# introAu.net
KiCad netlist of a schematic drawn in EAGLE
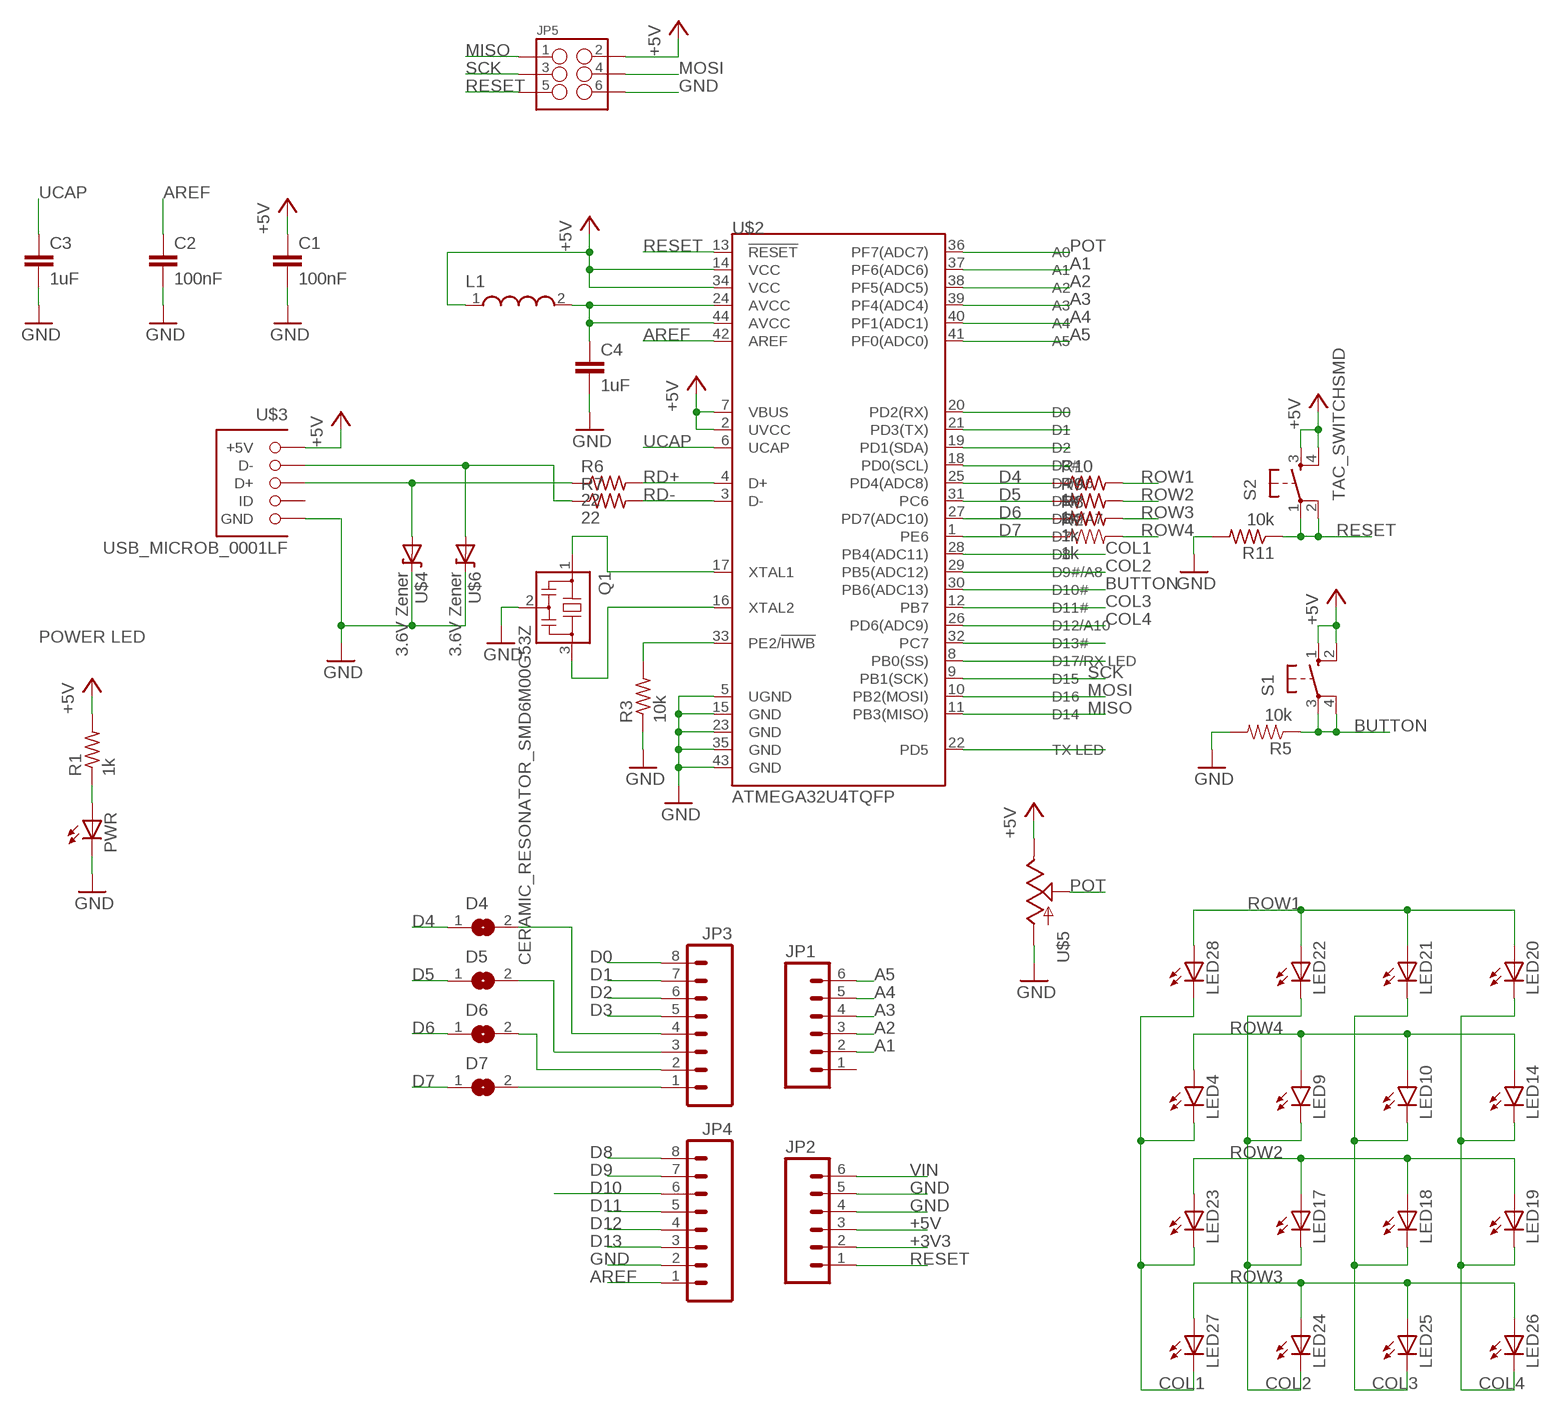
[diagram p0: schematic, sheet 1]

(export (version "E")
  (design (tool "Eeschema 10.0.6"))
  (components
    (comp (ref "C1")
      (value "100nF")
      (footprint "eagle-import:C0805")
      (libsource (lib "eagle-import") (part "C-EUC0805"))
    )
    (comp (ref "C2")
      (value "100nF")
      (footprint "eagle-import:C0805")
      (libsource (lib "eagle-import") (part "C-EUC0805"))
    )
    (comp (ref "C3")
      (value "1uF")
      (footprint "eagle-import:C0805")
      (libsource (lib "eagle-import") (part "C-EUC0805"))
    )
    (comp (ref "C4")
      (value "1uF")
      (footprint "eagle-import:C0805")
      (libsource (lib "eagle-import") (part "C-EUC0805"))
    )
    (comp (ref "D4") (value "SJ") (footprint "eagle-import:SJ") (libsource (lib "eagle-import") (part "SJ")))
    (comp (ref "D5") (value "SJ") (footprint "eagle-import:SJ") (libsource (lib "eagle-import") (part "SJ")))
    (comp (ref "D6") (value "SJ") (footprint "eagle-import:SJ") (libsource (lib "eagle-import") (part "SJ")))
    (comp (ref "D7") (value "SJ") (footprint "eagle-import:SJ") (libsource (lib "eagle-import") (part "SJ")))
    (comp (ref "JP1")
      (value "M06SMD-STRAIGHT-COMBO")
      (footprint "eagle-import:1X06_SMD_STRAIGHT_COMBO")
      (libsource (lib "eagle-import") (part "M06SMD-STRAIGHT-COMBO"))
    )
    (comp (ref "JP2")
      (value "M06SMD-STRAIGHT-COMBO")
      (footprint "eagle-import:1X06_SMD_STRAIGHT_COMBO")
      (libsource (lib "eagle-import") (part "M06SMD-STRAIGHT-COMBO"))
    )
    (comp (ref "JP3")
      (value "M08SMD-COMBO")
      (footprint "eagle-import:1X08_SMD_COMBINED")
      (libsource (lib "eagle-import") (part "M08SMD-COMBO"))
    )
    (comp (ref "JP4")
      (value "M08SMD-COMBO")
      (footprint "eagle-import:1X08_SMD_COMBINED")
      (libsource (lib "eagle-import") (part "M08SMD-COMBO"))
    )
    (comp (ref "JP5")
      (value "M03X22X3_SILK_SM")
      (footprint "eagle-import:2X3")
      (libsource (lib "eagle-import") (part "M03X22X3_SILK_SM"))
    )
    (comp (ref "L1")
      (value "WE-CBF_0805(WB/HS)")
      (footprint "eagle-import:WE-CBF_0805(W=3.0)")
      (libsource (lib "eagle-import") (part "WE-CBF_0805(WB/HS)"))
    )
    (comp (ref "LED4")
      (value "LED5MM")
      (footprint "eagle-import:LED5MM")
      (libsource (lib "eagle-import") (part "LED5MM"))
    )
    (comp (ref "LED9")
      (value "LED5MM")
      (footprint "eagle-import:LED5MM")
      (libsource (lib "eagle-import") (part "LED5MM"))
    )
    (comp (ref "LED10")
      (value "LED5MM")
      (footprint "eagle-import:LED5MM")
      (libsource (lib "eagle-import") (part "LED5MM"))
    )
    (comp (ref "LED14")
      (value "LED5MM")
      (footprint "eagle-import:LED5MM")
      (libsource (lib "eagle-import") (part "LED5MM"))
    )
    (comp (ref "LED17")
      (value "LEDCHIPLED_0805")
      (footprint "eagle-import:CHIPLED_0805")
      (libsource (lib "eagle-import") (part "LEDCHIPLED_0805"))
    )
    (comp (ref "LED18")
      (value "LEDCHIPLED_0805")
      (footprint "eagle-import:CHIPLED_0805")
      (libsource (lib "eagle-import") (part "LEDCHIPLED_0805"))
    )
    (comp (ref "LED19")
      (value "LEDCHIPLED_0805")
      (footprint "eagle-import:CHIPLED_0805")
      (libsource (lib "eagle-import") (part "LEDCHIPLED_0805"))
    )
    (comp (ref "LED20")
      (value "LEDCHIPLED_0805")
      (footprint "eagle-import:CHIPLED_0805")
      (libsource (lib "eagle-import") (part "LEDCHIPLED_0805"))
    )
    (comp (ref "LED21")
      (value "LEDCHIPLED_0805")
      (footprint "eagle-import:CHIPLED_0805")
      (libsource (lib "eagle-import") (part "LEDCHIPLED_0805"))
    )
    (comp (ref "LED22")
      (value "LEDCHIPLED_0805")
      (footprint "eagle-import:CHIPLED_0805")
      (libsource (lib "eagle-import") (part "LEDCHIPLED_0805"))
    )
    (comp (ref "LED23")
      (value "LEDCHIPLED_0805")
      (footprint "eagle-import:CHIPLED_0805")
      (libsource (lib "eagle-import") (part "LEDCHIPLED_0805"))
    )
    (comp (ref "LED24")
      (value "LEDCHIPLED_0805")
      (footprint "eagle-import:CHIPLED_0805")
      (libsource (lib "eagle-import") (part "LEDCHIPLED_0805"))
    )
    (comp (ref "LED25")
      (value "LEDCHIPLED_0805")
      (footprint "eagle-import:CHIPLED_0805")
      (libsource (lib "eagle-import") (part "LEDCHIPLED_0805"))
    )
    (comp (ref "LED26")
      (value "LEDCHIPLED_0805")
      (footprint "eagle-import:CHIPLED_0805")
      (libsource (lib "eagle-import") (part "LEDCHIPLED_0805"))
    )
    (comp (ref "LED27")
      (value "LEDCHIPLED_0805")
      (footprint "eagle-import:CHIPLED_0805")
      (libsource (lib "eagle-import") (part "LEDCHIPLED_0805"))
    )
    (comp (ref "LED28")
      (value "LEDCHIPLED_0805")
      (footprint "eagle-import:CHIPLED_0805")
      (libsource (lib "eagle-import") (part "LEDCHIPLED_0805"))
    )
    (comp (ref "PWR")
      (value "LEDCHIPLED_0805")
      (footprint "eagle-import:CHIPLED_0805")
      (libsource (lib "eagle-import") (part "LEDCHIPLED_0805"))
    )
    (comp (ref "Q1")
      (value "CERAMIC_RESONATOR_SMD6M00G53Z")
      (footprint "eagle-import:CERAMIC_RESONATOR_SMD")
      (fields (field (name "MPN") "CSTCR6M00G53-R0"))
      (libsource (lib "eagle-import") (part "CERAMIC_RESONATOR_SMD6M00G53Z"))
    )
    (comp (ref "R1")
      (value "1k")
      (footprint "eagle-import:R0805")
      (libsource (lib "eagle-import") (part "R-US_R0805"))
    )
    (comp (ref "R2")
      (value "1k")
      (footprint "eagle-import:AXIAL-0.3EZ")
      (libsource (lib "eagle-import") (part "1KOHM1/4W5%(PTH)HORIZ-KIT"))
    )
    (comp (ref "R3")
      (value "10k")
      (footprint "eagle-import:R0805")
      (libsource (lib "eagle-import") (part "R-US_R0805"))
    )
    (comp (ref "R5")
      (value "10k")
      (footprint "eagle-import:AXIAL-0.3EZ")
      (libsource (lib "eagle-import") (part "1KOHM1/4W5%(PTH)HORIZ-KIT"))
    )
    (comp (ref "R6")
      (value "22")
      (footprint "eagle-import:R0805")
      (libsource (lib "eagle-import") (part "R-US_R0805"))
    )
    (comp (ref "R7")
      (value "22")
      (footprint "eagle-import:R0805")
      (libsource (lib "eagle-import") (part "R-US_R0805"))
    )
    (comp (ref "R8")
      (value "1k")
      (footprint "eagle-import:R0805")
      (libsource (lib "eagle-import") (part "R-US_R0805"))
    )
    (comp (ref "R9")
      (value "1k")
      (footprint "eagle-import:R0805")
      (libsource (lib "eagle-import") (part "R-US_R0805"))
    )
    (comp (ref "R10")
      (value "1k")
      (footprint "eagle-import:R0805")
      (libsource (lib "eagle-import") (part "R-US_R0805"))
    )
    (comp (ref "R11")
      (value "10k")
      (footprint "eagle-import:R0805")
      (libsource (lib "eagle-import") (part "R-US_R0805"))
    )
    (comp (ref "S1")
      (value "TACT_BUTTON")
      (footprint "eagle-import:B3F-10XX")
      (fields (field (name "MPN") "B3F-1000"))
      (libsource (lib "eagle-import") (part "TACT_BUTTON"))
    )
    (comp (ref "S2")
      (value "TAC_SWITCHSMD")
      (footprint "eagle-import:TACTILE-SWITCH-SMD")
      (libsource (lib "eagle-import") (part "TAC_SWITCHSMD"))
    )
    (comp (ref "U$2")
      (value "ATMEGA32U4TQFP")
      (footprint "eagle-import:SPARKFUN-DIGITALIC_TQFP44")
      (libsource (lib "eagle-import") (part "ATMEGA32U4TQFP"))
    )
    (comp (ref "U$3")
      (value "USB_MICROB_0001LF")
      (footprint "eagle-import:USB_MICROB_CHEAPER")
      (libsource (lib "eagle-import") (part "USB_MICROB_0001LF"))
    )
    (comp (ref "U$4")
      (value "3.6V Zener")
      (footprint "eagle-import:SOD-323")
      (libsource (lib "eagle-import") (part "DIODE-ZENER-BZT52"))
    )
    (comp (ref "U$5")
      (value "POT")
      (footprint "eagle-import:ALPS_POT")
      (libsource (lib "eagle-import") (part "POT"))
    )
    (comp (ref "U$6")
      (value "3.6V Zener")
      (footprint "eagle-import:SOD-323")
      (libsource (lib "eagle-import") (part "DIODE-ZENER-BZT52"))
    )
  )
  (nets
    (net (code "1") (name "+5V") (class "Default")
      (node (ref "C1") (pin "1") (pinfunction "1_1") (pintype "passive"))
      (node (ref "JP2") (pin "3") (pinfunction "3_3") (pintype "passive"))
      (node (ref "JP5") (pin "2") (pinfunction "2_2") (pintype "bidirectional"))
      (node (ref "L1") (pin "1") (pinfunction "1_1") (pintype "passive"))
      (node (ref "R1") (pin "2") (pinfunction "2_2") (pintype "passive"))
      (node (ref "S1") (pin "1") (pinfunction "S_1") (pintype "passive"))
      (node (ref "S1") (pin "2") (pinfunction "S1_2") (pintype "passive"))
      (node (ref "S2") (pin "3") (pinfunction "3_3") (pintype "passive"))
      (node (ref "S2") (pin "4") (pinfunction "4_4") (pintype "passive"))
      (node (ref "U$2") (pin "14") (pinfunction "VCC_14") (pintype "bidirectional"))
      (node (ref "U$2") (pin "2") (pinfunction "UVCC_2") (pintype "bidirectional"))
      (node (ref "U$2") (pin "34") (pinfunction "VCC_34") (pintype "bidirectional"))
      (node (ref "U$2") (pin "7") (pinfunction "VBUS_7") (pintype "bidirectional"))
      (node (ref "U$3") (pin "P$1") (pinfunction "+5V_P$1") (pintype "bidirectional"))
      (node (ref "U$5") (pin "P$1") (pinfunction "E_P$1") (pintype "passive"))
    )
    (net (code "2") (name "/+3V3") (class "Default")
      (node (ref "JP2") (pin "2") (pinfunction "2_2") (pintype "passive"))
    )
    (net (code "3") (name "/A1") (class "Default")
      (node (ref "JP1") (pin "2") (pinfunction "2_2") (pintype "passive"))
      (node (ref "U$2") (pin "37") (pinfunction "PF6(ADC6)_37") (pintype "bidirectional"))
    )
    (net (code "4") (name "/A2") (class "Default")
      (node (ref "JP1") (pin "3") (pinfunction "3_3") (pintype "passive"))
      (node (ref "U$2") (pin "38") (pinfunction "PF5(ADC5)_38") (pintype "bidirectional"))
    )
    (net (code "5") (name "/A3") (class "Default")
      (node (ref "JP1") (pin "4") (pinfunction "4_4") (pintype "passive"))
      (node (ref "U$2") (pin "39") (pinfunction "PF4(ADC4)_39") (pintype "bidirectional"))
    )
    (net (code "6") (name "/A4") (class "Default")
      (node (ref "JP1") (pin "5") (pinfunction "5_5") (pintype "passive"))
      (node (ref "U$2") (pin "40") (pinfunction "PF1(ADC1)_40") (pintype "bidirectional"))
    )
    (net (code "7") (name "/A5") (class "Default")
      (node (ref "JP1") (pin "6") (pinfunction "6_6") (pintype "passive"))
      (node (ref "U$2") (pin "41") (pinfunction "PF0(ADC0)_41") (pintype "bidirectional"))
    )
    (net (code "8") (name "/AREF") (class "Default")
      (node (ref "C2") (pin "1") (pinfunction "1_1") (pintype "passive"))
      (node (ref "JP4") (pin "1") (pinfunction "1_1") (pintype "passive"))
      (node (ref "U$2") (pin "42") (pinfunction "AREF_42") (pintype "bidirectional"))
    )
    (net (code "9") (name "/BUTTON") (class "Default")
      (node (ref "R5") (pin "P$1") (pinfunction "1_P$1") (pintype "passive"))
      (node (ref "S1") (pin "3") (pinfunction "P_3") (pintype "passive"))
      (node (ref "S1") (pin "4") (pinfunction "P1_4") (pintype "passive"))
      (node (ref "U$2") (pin "30") (pinfunction "PB6(ADC13)_30") (pintype "bidirectional"))
    )
    (net (code "10") (name "/COL1") (class "Default")
      (node (ref "LED23") (pin "C") (pinfunction "C_C") (pintype "passive"))
      (node (ref "LED27") (pin "C") (pinfunction "C_C") (pintype "passive"))
      (node (ref "LED28") (pin "C") (pinfunction "C_C") (pintype "passive"))
      (node (ref "LED4") (pin "K") (pinfunction "C_K") (pintype "passive"))
      (node (ref "U$2") (pin "28") (pinfunction "PB4(ADC11)_28") (pintype "bidirectional"))
    )
    (net (code "11") (name "/COL2") (class "Default")
      (node (ref "LED17") (pin "C") (pinfunction "C_C") (pintype "passive"))
      (node (ref "LED22") (pin "C") (pinfunction "C_C") (pintype "passive"))
      (node (ref "LED24") (pin "C") (pinfunction "C_C") (pintype "passive"))
      (node (ref "LED9") (pin "K") (pinfunction "C_K") (pintype "passive"))
      (node (ref "U$2") (pin "29") (pinfunction "PB5(ADC12)_29") (pintype "bidirectional"))
    )
    (net (code "12") (name "/COL3") (class "Default")
      (node (ref "LED10") (pin "K") (pinfunction "C_K") (pintype "passive"))
      (node (ref "LED18") (pin "C") (pinfunction "C_C") (pintype "passive"))
      (node (ref "LED21") (pin "C") (pinfunction "C_C") (pintype "passive"))
      (node (ref "LED25") (pin "C") (pinfunction "C_C") (pintype "passive"))
      (node (ref "U$2") (pin "12") (pinfunction "PB7_12") (pintype "bidirectional"))
    )
    (net (code "13") (name "/COL4") (class "Default")
      (node (ref "LED14") (pin "K") (pinfunction "C_K") (pintype "passive"))
      (node (ref "LED19") (pin "C") (pinfunction "C_C") (pintype "passive"))
      (node (ref "LED20") (pin "C") (pinfunction "C_C") (pintype "passive"))
      (node (ref "LED26") (pin "C") (pinfunction "C_C") (pintype "passive"))
      (node (ref "U$2") (pin "26") (pinfunction "PD6(ADC9)_26") (pintype "bidirectional"))
    )
    (net (code "14") (name "/D0") (class "Default")
      (node (ref "JP3") (pin "8") (pinfunction "8_8") (pintype "passive"))
      (node (ref "U$2") (pin "20") (pinfunction "PD2(RX)_20") (pintype "bidirectional"))
    )
    (net (code "15") (name "/D1") (class "Default")
      (node (ref "JP3") (pin "7") (pinfunction "7_7") (pintype "passive"))
      (node (ref "U$2") (pin "21") (pinfunction "PD3(TX)_21") (pintype "bidirectional"))
    )
    (net (code "16") (name "/D2") (class "Default")
      (node (ref "JP3") (pin "6") (pinfunction "6_6") (pintype "passive"))
      (node (ref "U$2") (pin "19") (pinfunction "PD1(SDA)_19") (pintype "bidirectional"))
    )
    (net (code "17") (name "/D3") (class "Default")
      (node (ref "JP3") (pin "5") (pinfunction "5_5") (pintype "passive"))
      (node (ref "U$2") (pin "18") (pinfunction "PD0(SCL)_18") (pintype "bidirectional"))
    )
    (net (code "18") (name "/D4") (class "Default")
      (node (ref "D4") (pin "1") (pinfunction "1_1") (pintype "passive"))
      (node (ref "R10") (pin "1") (pinfunction "1_1") (pintype "passive"))
      (node (ref "U$2") (pin "25") (pinfunction "PD4(ADC8)_25") (pintype "bidirectional"))
    )
    (net (code "19") (name "/D5") (class "Default")
      (node (ref "D5") (pin "1") (pinfunction "1_1") (pintype "passive"))
      (node (ref "R9") (pin "1") (pinfunction "1_1") (pintype "passive"))
      (node (ref "U$2") (pin "31") (pinfunction "PC6_31") (pintype "bidirectional"))
    )
    (net (code "20") (name "/D6") (class "Default")
      (node (ref "D6") (pin "1") (pinfunction "1_1") (pintype "passive"))
      (node (ref "R8") (pin "1") (pinfunction "1_1") (pintype "passive"))
      (node (ref "U$2") (pin "27") (pinfunction "PD7(ADC10)_27") (pintype "bidirectional"))
    )
    (net (code "21") (name "/D7") (class "Default")
      (node (ref "D7") (pin "1") (pinfunction "1_1") (pintype "passive"))
      (node (ref "R2") (pin "P$1") (pinfunction "1_P$1") (pintype "passive"))
      (node (ref "U$2") (pin "1") (pinfunction "PE6_1") (pintype "bidirectional"))
    )
    (net (code "22") (name "/D8") (class "Default")
      (node (ref "JP4") (pin "8") (pinfunction "8_8") (pintype "passive"))
    )
    (net (code "23") (name "/D9") (class "Default")
      (node (ref "JP4") (pin "7") (pinfunction "7_7") (pintype "passive"))
    )
    (net (code "24") (name "/D10") (class "Default")
      (node (ref "JP4") (pin "6") (pinfunction "6_6") (pintype "passive"))
    )
    (net (code "25") (name "/D11") (class "Default")
      (node (ref "JP4") (pin "5") (pinfunction "5_5") (pintype "passive"))
    )
    (net (code "26") (name "/D12") (class "Default")
      (node (ref "JP4") (pin "4") (pinfunction "4_4") (pintype "passive"))
    )
    (net (code "27") (name "/D13") (class "Default")
      (node (ref "JP4") (pin "3") (pinfunction "3_3") (pintype "passive"))
      (node (ref "U$2") (pin "32") (pinfunction "PC7_32") (pintype "bidirectional"))
    )
    (net (code "28") (name "/MISO") (class "Default")
      (node (ref "JP5") (pin "1") (pinfunction "1_1") (pintype "bidirectional"))
      (node (ref "U$2") (pin "11") (pinfunction "PB3(MISO)_11") (pintype "bidirectional"))
    )
    (net (code "29") (name "/MOSI") (class "Default")
      (node (ref "JP5") (pin "4") (pinfunction "4_4") (pintype "bidirectional"))
      (node (ref "U$2") (pin "10") (pinfunction "PB2(MOSI)_10") (pintype "bidirectional"))
    )
    (net (code "30") (name "/POT") (class "Default")
      (node (ref "U$2") (pin "36") (pinfunction "PF7(ADC7)_36") (pintype "bidirectional"))
      (node (ref "U$5") (pin "P$2") (pinfunction "S_P$2") (pintype "passive"))
    )
    (net (code "31") (name "/RD+") (class "Default")
      (node (ref "R6") (pin "2") (pinfunction "2_2") (pintype "passive"))
      (node (ref "U$2") (pin "4") (pinfunction "D+_4") (pintype "bidirectional"))
    )
    (net (code "32") (name "/RD-") (class "Default")
      (node (ref "R7") (pin "2") (pinfunction "2_2") (pintype "passive"))
      (node (ref "U$2") (pin "3") (pinfunction "D-_3") (pintype "bidirectional"))
    )
    (net (code "33") (name "/RESET") (class "Default")
      (node (ref "JP2") (pin "1") (pinfunction "1_1") (pintype "passive"))
      (node (ref "JP5") (pin "5") (pinfunction "5_5") (pintype "bidirectional"))
      (node (ref "R11") (pin "1") (pinfunction "1_1") (pintype "passive"))
      (node (ref "S2") (pin "1") (pinfunction "1_1") (pintype "passive"))
      (node (ref "S2") (pin "2") (pinfunction "2_2") (pintype "passive"))
      (node (ref "U$2") (pin "13") (pinfunction "~{RESET}_13") (pintype "bidirectional"))
    )
    (net (code "34") (name "/ROW1") (class "Default")
      (node (ref "LED20") (pin "A") (pinfunction "A_A") (pintype "passive"))
      (node (ref "LED21") (pin "A") (pinfunction "A_A") (pintype "passive"))
      (node (ref "LED22") (pin "A") (pinfunction "A_A") (pintype "passive"))
      (node (ref "LED28") (pin "A") (pinfunction "A_A") (pintype "passive"))
      (node (ref "R10") (pin "2") (pinfunction "2_2") (pintype "passive"))
    )
    (net (code "35") (name "/ROW2") (class "Default")
      (node (ref "LED17") (pin "A") (pinfunction "A_A") (pintype "passive"))
      (node (ref "LED18") (pin "A") (pinfunction "A_A") (pintype "passive"))
      (node (ref "LED19") (pin "A") (pinfunction "A_A") (pintype "passive"))
      (node (ref "LED23") (pin "A") (pinfunction "A_A") (pintype "passive"))
      (node (ref "R9") (pin "2") (pinfunction "2_2") (pintype "passive"))
    )
    (net (code "36") (name "/ROW3") (class "Default")
      (node (ref "LED24") (pin "A") (pinfunction "A_A") (pintype "passive"))
      (node (ref "LED25") (pin "A") (pinfunction "A_A") (pintype "passive"))
      (node (ref "LED26") (pin "A") (pinfunction "A_A") (pintype "passive"))
      (node (ref "LED27") (pin "A") (pinfunction "A_A") (pintype "passive"))
      (node (ref "R8") (pin "2") (pinfunction "2_2") (pintype "passive"))
    )
    (net (code "37") (name "/ROW4") (class "Default")
      (node (ref "LED10") (pin "A") (pinfunction "A_A") (pintype "passive"))
      (node (ref "LED14") (pin "A") (pinfunction "A_A") (pintype "passive"))
      (node (ref "LED4") (pin "A") (pinfunction "A_A") (pintype "passive"))
      (node (ref "LED9") (pin "A") (pinfunction "A_A") (pintype "passive"))
      (node (ref "R2") (pin "P$2") (pinfunction "2_P$2") (pintype "passive"))
    )
    (net (code "38") (name "/SCK") (class "Default")
      (node (ref "JP5") (pin "3") (pinfunction "3_3") (pintype "bidirectional"))
      (node (ref "U$2") (pin "9") (pinfunction "PB1(SCK)_9") (pintype "bidirectional"))
    )
    (net (code "39") (name "/UCAP") (class "Default")
      (node (ref "C3") (pin "1") (pinfunction "1_1") (pintype "passive"))
      (node (ref "U$2") (pin "6") (pinfunction "UCAP_6") (pintype "bidirectional"))
    )
    (net (code "40") (name "/VIN") (class "Default")
      (node (ref "JP2") (pin "6") (pinfunction "6_6") (pintype "passive"))
    )
    (net (code "41") (name "GND") (class "Default")
      (node (ref "C1") (pin "2") (pinfunction "2_2") (pintype "passive"))
      (node (ref "C2") (pin "2") (pinfunction "2_2") (pintype "passive"))
      (node (ref "C3") (pin "2") (pinfunction "2_2") (pintype "passive"))
      (node (ref "C4") (pin "2") (pinfunction "2_2") (pintype "passive"))
      (node (ref "JP2") (pin "4") (pinfunction "4_4") (pintype "passive"))
      (node (ref "JP2") (pin "5") (pinfunction "5_5") (pintype "passive"))
      (node (ref "JP4") (pin "2") (pinfunction "2_2") (pintype "passive"))
      (node (ref "JP5") (pin "6") (pinfunction "6_6") (pintype "bidirectional"))
      (node (ref "PWR") (pin "C") (pinfunction "C_C") (pintype "passive"))
      (node (ref "Q1") (pin "2") (pinfunction "2_2") (pintype "passive"))
      (node (ref "R11") (pin "2") (pinfunction "2_2") (pintype "passive"))
      (node (ref "R3") (pin "1") (pinfunction "1_1") (pintype "passive"))
      (node (ref "R5") (pin "P$2") (pinfunction "2_P$2") (pintype "passive"))
      (node (ref "U$2") (pin "15") (pinfunction "GND_15") (pintype "bidirectional"))
      (node (ref "U$2") (pin "23") (pinfunction "GND_23") (pintype "bidirectional"))
      (node (ref "U$2") (pin "35") (pinfunction "GND_35") (pintype "bidirectional"))
      (node (ref "U$2") (pin "43") (pinfunction "GND_43") (pintype "bidirectional"))
      (node (ref "U$2") (pin "5") (pinfunction "UGND_5") (pintype "bidirectional"))
      (node (ref "U$3") (pin "P$4") (pinfunction "GND_P$4") (pintype "bidirectional"))
      (node (ref "U$4") (pin "1") (pinfunction "C_1") (pintype "passive"))
      (node (ref "U$5") (pin "P$3") (pinfunction "A_P$3") (pintype "passive"))
      (node (ref "U$6") (pin "1") (pinfunction "C_1") (pintype "passive"))
    )
    (net (code "42") (name "Net-(C4-Pad1)") (class "Default")
      (node (ref "C4") (pin "1") (pinfunction "1_1") (pintype "passive"))
      (node (ref "L1") (pin "2") (pinfunction "2_2") (pintype "passive"))
      (node (ref "U$2") (pin "24") (pinfunction "AVCC_24") (pintype "bidirectional"))
      (node (ref "U$2") (pin "44") (pinfunction "AVCC_44") (pintype "bidirectional"))
    )
    (net (code "43") (name "Net-(D4-Pad2)") (class "Default")
      (node (ref "D4") (pin "2") (pinfunction "2_2") (pintype "passive"))
      (node (ref "JP3") (pin "4") (pinfunction "4_4") (pintype "passive"))
    )
    (net (code "44") (name "Net-(D5-Pad2)") (class "Default")
      (node (ref "D5") (pin "2") (pinfunction "2_2") (pintype "passive"))
      (node (ref "JP3") (pin "3") (pinfunction "3_3") (pintype "passive"))
    )
    (net (code "45") (name "Net-(D6-Pad2)") (class "Default")
      (node (ref "D6") (pin "2") (pinfunction "2_2") (pintype "passive"))
      (node (ref "JP3") (pin "2") (pinfunction "2_2") (pintype "passive"))
    )
    (net (code "46") (name "Net-(D7-Pad2)") (class "Default")
      (node (ref "D7") (pin "2") (pinfunction "2_2") (pintype "passive"))
      (node (ref "JP3") (pin "1") (pinfunction "1_1") (pintype "passive"))
    )
    (net (code "47") (name "Net-(PWR-PadA)") (class "Default")
      (node (ref "PWR") (pin "A") (pinfunction "A_A") (pintype "passive"))
      (node (ref "R1") (pin "1") (pinfunction "1_1") (pintype "passive"))
    )
    (net (code "48") (name "Net-(U$2-PE2{slash}~{HWB})") (class "Default")
      (node (ref "R3") (pin "2") (pinfunction "2_2") (pintype "passive"))
      (node (ref "U$2") (pin "33") (pinfunction "PE2/~{HWB}_33") (pintype "bidirectional"))
    )
    (net (code "49") (name "Net-(U$2-XTAL1)") (class "Default")
      (node (ref "Q1") (pin "1") (pinfunction "1_1") (pintype "passive"))
      (node (ref "U$2") (pin "17") (pinfunction "XTAL1_17") (pintype "bidirectional"))
    )
    (net (code "50") (name "Net-(U$2-XTAL2)") (class "Default")
      (node (ref "Q1") (pin "3") (pinfunction "3_3") (pintype "passive"))
      (node (ref "U$2") (pin "16") (pinfunction "XTAL2_16") (pintype "bidirectional"))
    )
    (net (code "51") (name "Net-(U$3-D+)") (class "Default")
      (node (ref "R6") (pin "1") (pinfunction "1_1") (pintype "passive"))
      (node (ref "U$3") (pin "P$3") (pinfunction "D+_P$3") (pintype "bidirectional"))
      (node (ref "U$4") (pin "2") (pinfunction "A_2") (pintype "passive"))
    )
    (net (code "52") (name "Net-(U$3-D-)") (class "Default")
      (node (ref "R7") (pin "1") (pinfunction "1_1") (pintype "passive"))
      (node (ref "U$3") (pin "P$2") (pinfunction "D-_P$2") (pintype "bidirectional"))
      (node (ref "U$6") (pin "2") (pinfunction "A_2") (pintype "passive"))
    )
    (net (code "53") (name "unconnected-(JP1-Pad1)") (class "Default")
      (node (ref "JP1") (pin "1") (pinfunction "1_1") (pintype "passive"))
    )
    (net (code "54") (name "unconnected-(U$2-PB0(SS)-Pad8)") (class "Default")
      (node (ref "U$2") (pin "8") (pinfunction "PB0(SS)_8") (pintype "bidirectional"))
    )
    (net (code "55") (name "unconnected-(U$2-PD5-Pad22)") (class "Default")
      (node (ref "U$2") (pin "22") (pinfunction "PD5_22") (pintype "bidirectional"))
    )
    (net (code "56") (name "unconnected-(U$3-ID-PadP$5)") (class "Default")
      (node (ref "U$3") (pin "P$5") (pinfunction "ID_P$5") (pintype "bidirectional"))
    )
  )
)
